# flippie.net
KiCad netlist of a schematic drawn in EAGLE
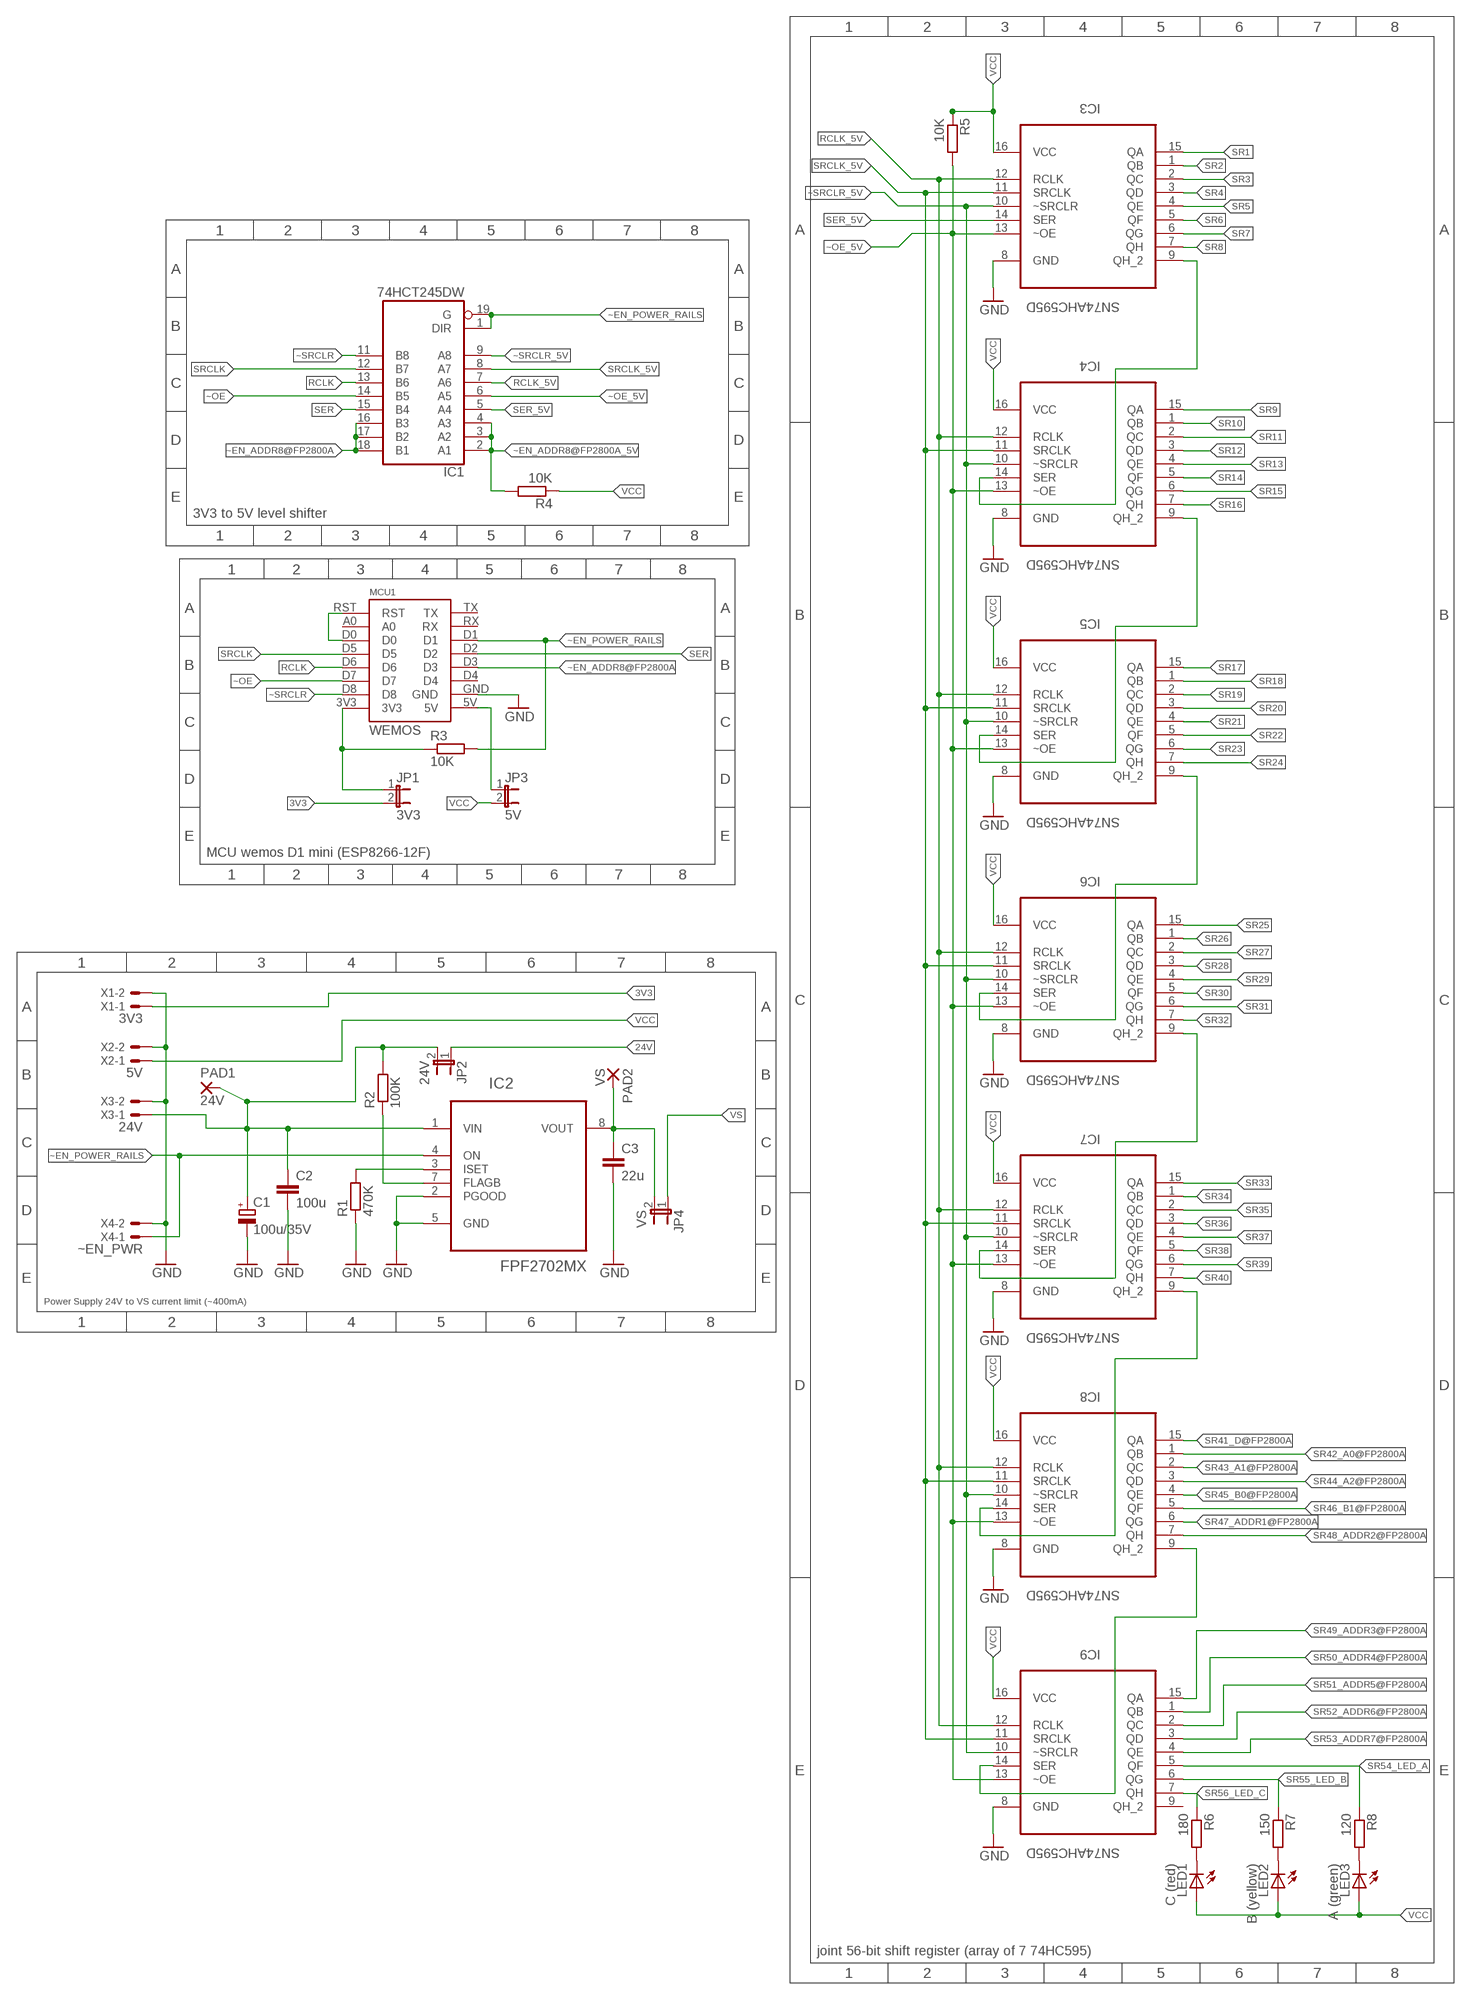
[diagram p0: schematic, sheet 1, part 1 of 2]
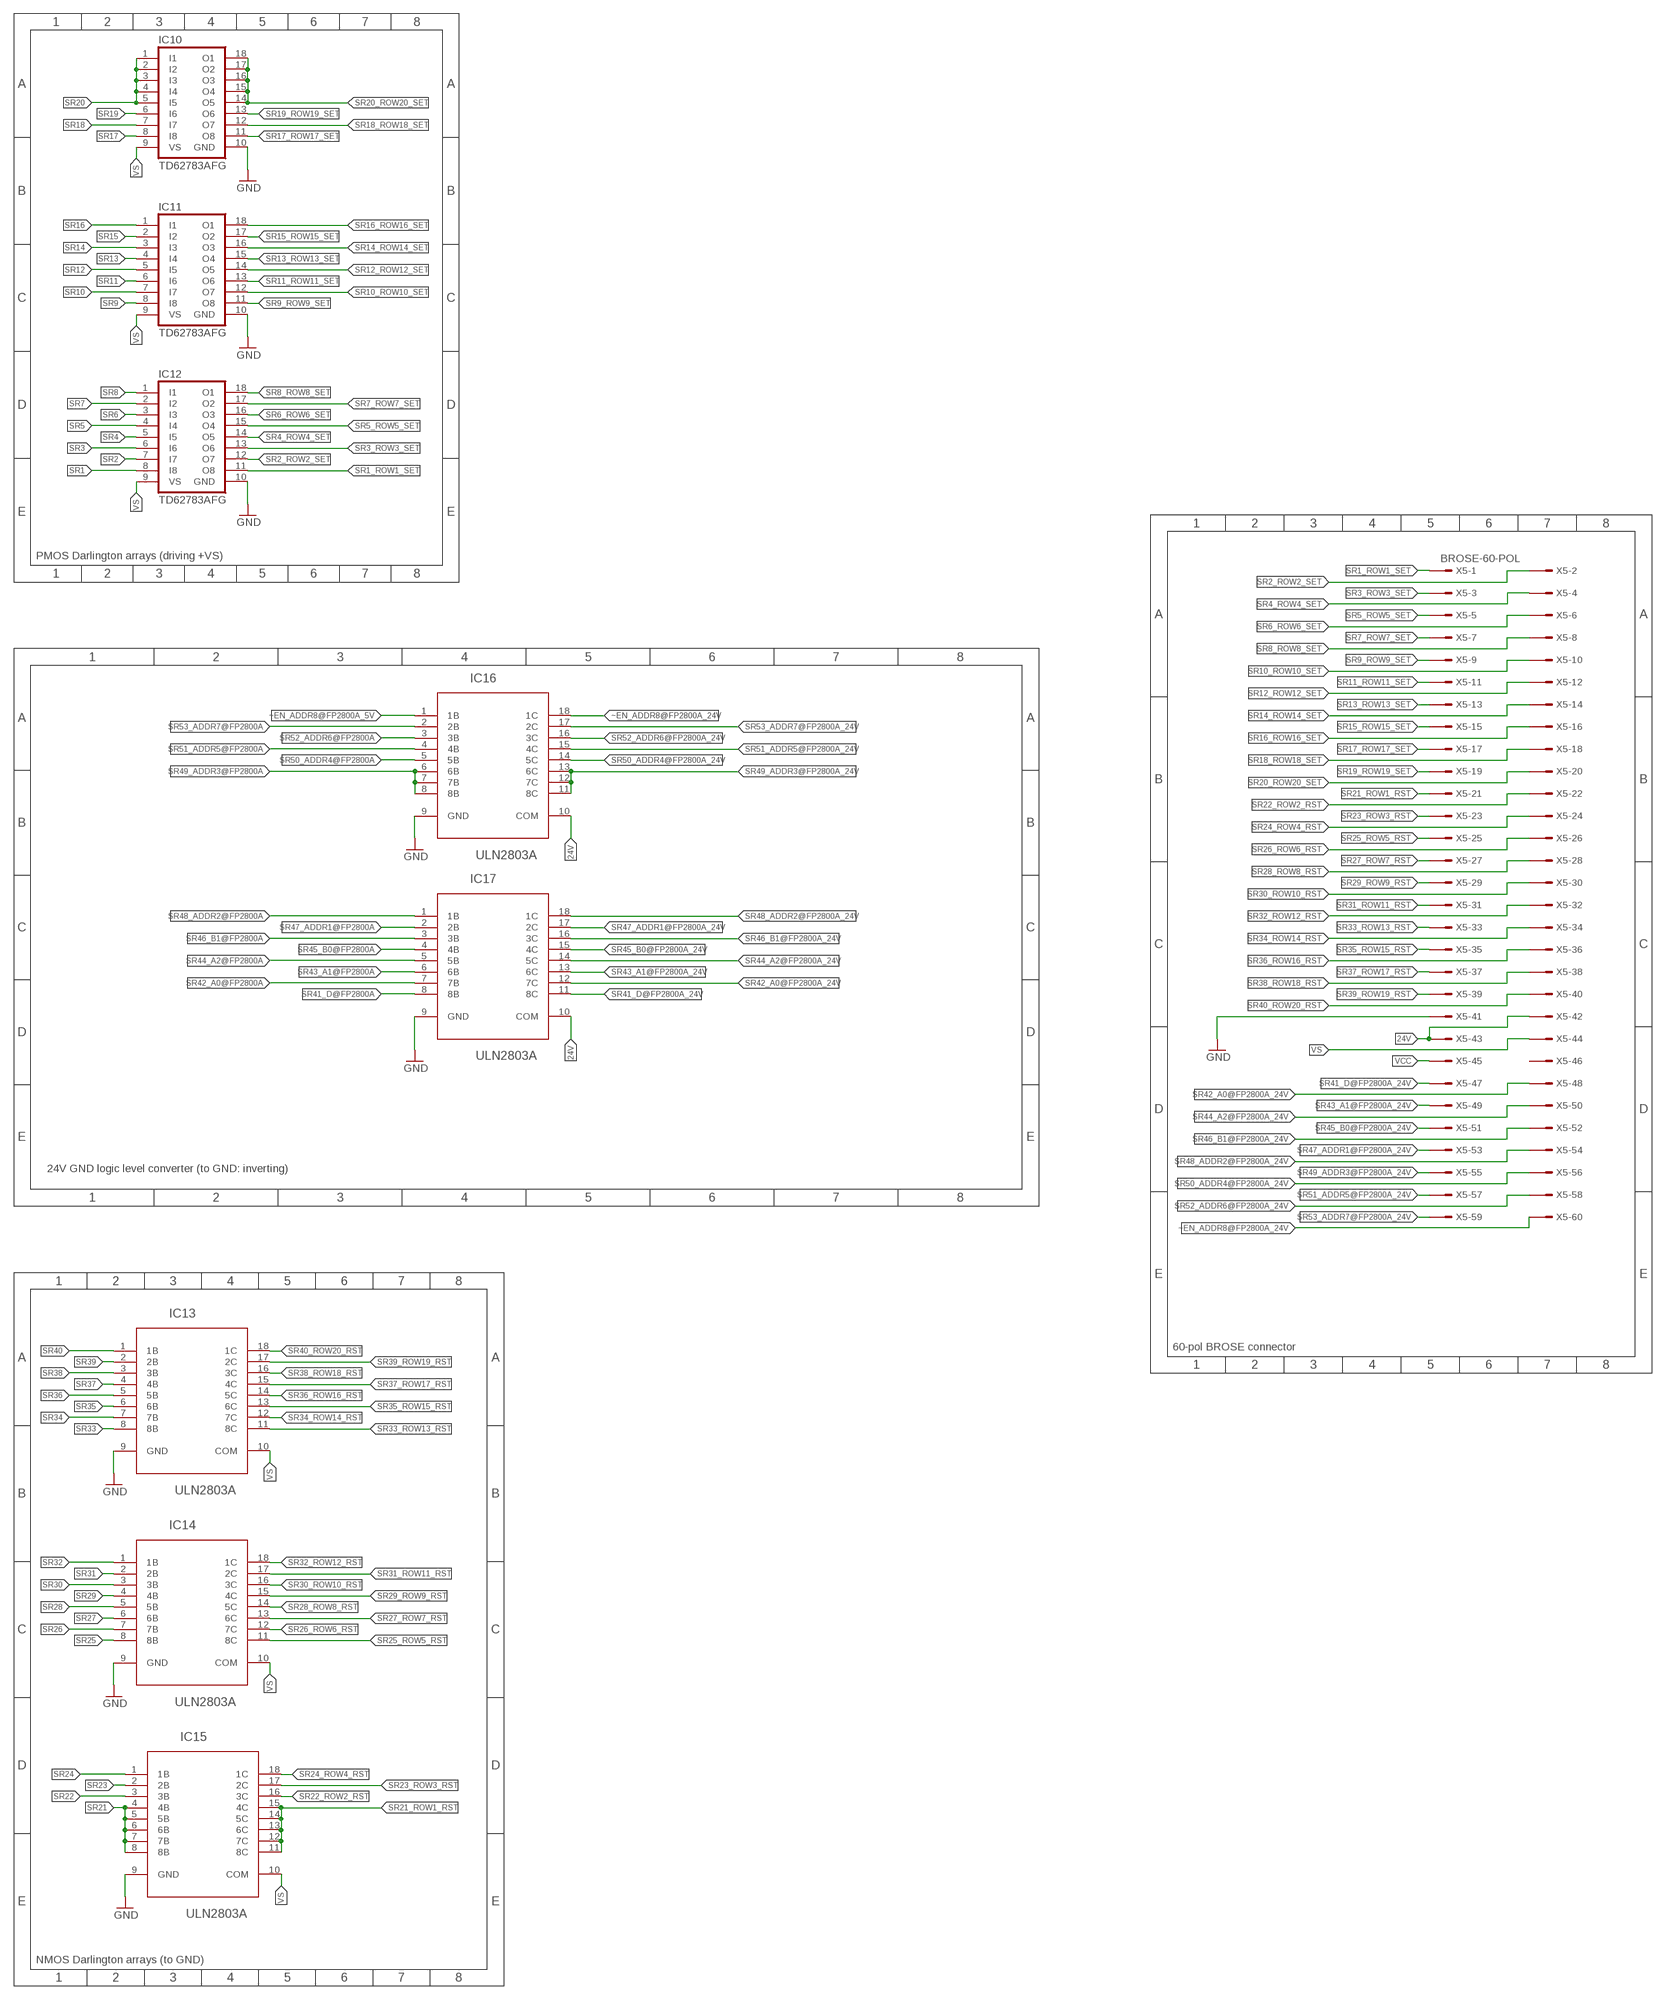
[diagram p1: schematic, sheet 1, part 2 of 2]

(export (version "E")
  (design (tool "Eeschema 10.0.6"))
  (components
    (comp (ref "C1")
      (value "100u/35V")
      (footprint "eagle-import:PANASONIC_E")
      (libsource (lib "eagle-import") (part "CPOL-EUE"))
    )
    (comp (ref "C2")
      (value "100u")
      (footprint "eagle-import:C1206")
      (libsource (lib "eagle-import") (part "C-EUC1206"))
    )
    (comp (ref "C3")
      (value "22u")
      (footprint "eagle-import:C1206")
      (libsource (lib "eagle-import") (part "C-EUC1206"))
    )
    (comp (ref "IC1")
      (value "74HCT245DW")
      (footprint "eagle-import:SO20W")
      (libsource (lib "eagle-import") (part "74245DWHCT"))
    )
    (comp (ref "IC2")
      (value "FPF2702MX")
      (footprint "eagle-import:SOIC127P600X175-8N")
      (libsource (lib "eagle-import") (part "FPF2700"))
    )
    (comp (ref "IC3")
      (value "SN74AHC595D")
      (footprint "eagle-import:SOIC127P600X175-16N")
      (libsource (lib "eagle-import") (part "SN74AHC595D"))
    )
    (comp (ref "IC4")
      (value "SN74AHC595D")
      (footprint "eagle-import:SOIC127P600X175-16N")
      (libsource (lib "eagle-import") (part "SN74AHC595D"))
    )
    (comp (ref "IC5")
      (value "SN74AHC595D")
      (footprint "eagle-import:SOIC127P600X175-16N")
      (libsource (lib "eagle-import") (part "SN74AHC595D"))
    )
    (comp (ref "IC6")
      (value "SN74AHC595D")
      (footprint "eagle-import:SOIC127P600X175-16N")
      (libsource (lib "eagle-import") (part "SN74AHC595D"))
    )
    (comp (ref "IC7")
      (value "SN74AHC595D")
      (footprint "eagle-import:SOIC127P600X175-16N")
      (libsource (lib "eagle-import") (part "SN74AHC595D"))
    )
    (comp (ref "IC8")
      (value "SN74AHC595D")
      (footprint "eagle-import:SOIC127P600X175-16N")
      (libsource (lib "eagle-import") (part "SN74AHC595D"))
    )
    (comp (ref "IC9")
      (value "SN74AHC595D")
      (footprint "eagle-import:SOIC127P600X175-16N")
      (libsource (lib "eagle-import") (part "SN74AHC595D"))
    )
    (comp (ref "IC10")
      (value "TD62783AFG")
      (footprint "eagle-import:SO18W")
      (libsource (lib "eagle-import") (part "UDN298LW1"))
    )
    (comp (ref "IC11")
      (value "TD62783AFG")
      (footprint "eagle-import:SO18W")
      (libsource (lib "eagle-import") (part "UDN298LW1"))
    )
    (comp (ref "IC12")
      (value "TD62783AFG")
      (footprint "eagle-import:SO18W")
      (libsource (lib "eagle-import") (part "UDN298LW1"))
    )
    (comp (ref "IC13")
      (value "ULN2803A")
      (footprint "eagle-import:SOIC127P1030X265-18N")
      (fields (field (name "MPN") "ULN2803ADW"))
      (libsource (lib "eagle-import") (part "ULN2803ADW"))
    )
    (comp (ref "IC14")
      (value "ULN2803A")
      (footprint "eagle-import:SOIC127P1030X265-18N")
      (fields (field (name "MPN") "ULN2803ADW"))
      (libsource (lib "eagle-import") (part "ULN2803ADW"))
    )
    (comp (ref "IC15")
      (value "ULN2803A")
      (footprint "eagle-import:SOIC127P1030X265-18N")
      (fields (field (name "MPN") "ULN2803ADW"))
      (libsource (lib "eagle-import") (part "ULN2803ADW"))
    )
    (comp (ref "IC16")
      (value "ULN2803A")
      (footprint "eagle-import:SOIC127P1030X265-18N")
      (fields (field (name "MPN") "ULN2803ADW"))
      (libsource (lib "eagle-import") (part "ULN2803ADW"))
    )
    (comp (ref "IC17")
      (value "ULN2803A")
      (footprint "eagle-import:SOIC127P1030X265-18N")
      (fields (field (name "MPN") "ULN2803ADW"))
      (libsource (lib "eagle-import") (part "ULN2803ADW"))
    )
    (comp (ref "JP1")
      (value "3V3")
      (footprint "eagle-import:JP1")
      (libsource (lib "eagle-import") (part "JP1E"))
    )
    (comp (ref "JP2")
      (value "24V")
      (footprint "eagle-import:JP1")
      (libsource (lib "eagle-import") (part "JP1E"))
    )
    (comp (ref "JP3")
      (value "5V")
      (footprint "eagle-import:JP1")
      (libsource (lib "eagle-import") (part "JP1E"))
    )
    (comp (ref "JP4")
      (value "VS")
      (footprint "eagle-import:JP1")
      (libsource (lib "eagle-import") (part "JP1E"))
    )
    (comp (ref "LED1")
      (value "C (red)")
      (footprint "eagle-import:1206")
      (libsource (lib "eagle-import") (part "LEDSMT1206"))
    )
    (comp (ref "LED2")
      (value "B (yellow)")
      (footprint "eagle-import:1206")
      (libsource (lib "eagle-import") (part "LEDSMT1206"))
    )
    (comp (ref "LED3")
      (value "A (green)")
      (footprint "eagle-import:1206")
      (libsource (lib "eagle-import") (part "LEDSMT1206"))
    )
    (comp (ref "MCU1")
      (value "WEMOS")
      (footprint "eagle-import:WEMOS")
      (libsource (lib "eagle-import") (part "WEMOS"))
    )
    (comp (ref "PAD1")
      (value "24V")
      (footprint "eagle-import:2,15_1,0")
      (libsource (lib "eagle-import") (part "2,15/1,0"))
    )
    (comp (ref "PAD2")
      (value "VS")
      (footprint "eagle-import:2,15_1,0")
      (libsource (lib "eagle-import") (part "2,15/1,0"))
    )
    (comp (ref "R1")
      (value "470K")
      (footprint "eagle-import:R1206")
      (libsource (lib "eagle-import") (part "R-EU_R1206"))
    )
    (comp (ref "R2")
      (value "100K")
      (footprint "eagle-import:R1206")
      (libsource (lib "eagle-import") (part "R-EU_R1206"))
    )
    (comp (ref "R3")
      (value "10K")
      (footprint "eagle-import:R1206")
      (libsource (lib "eagle-import") (part "R-EU_R1206"))
    )
    (comp (ref "R4")
      (value "10K")
      (footprint "eagle-import:R1206")
      (libsource (lib "eagle-import") (part "R-EU_R1206"))
    )
    (comp (ref "R5")
      (value "10K")
      (footprint "eagle-import:R1206")
      (libsource (lib "eagle-import") (part "R-EU_R1206"))
    )
    (comp (ref "R6")
      (value "180")
      (footprint "eagle-import:R1206")
      (libsource (lib "eagle-import") (part "R-EU_R1206"))
    )
    (comp (ref "R7")
      (value "150")
      (footprint "eagle-import:R1206")
      (libsource (lib "eagle-import") (part "R-EU_R1206"))
    )
    (comp (ref "R8")
      (value "120")
      (footprint "eagle-import:R1206")
      (libsource (lib "eagle-import") (part "R-EU_R1206"))
    )
    (comp (ref "X1")
      (value "3V3")
      (footprint "eagle-import:JST-XH-02-PACKAGE-LONG-PAD")
      (libsource (lib "eagle-import") (part "JST-XH-02-PIN-LONG-PAD"))
    )
    (comp (ref "X2")
      (value "5V")
      (footprint "eagle-import:JST-XH-02-PACKAGE-LONG-PAD")
      (libsource (lib "eagle-import") (part "JST-XH-02-PIN-LONG-PAD"))
    )
    (comp (ref "X3")
      (value "24V")
      (footprint "eagle-import:JST-XH-02-PACKAGE-LONG-PAD")
      (libsource (lib "eagle-import") (part "JST-XH-02-PIN-LONG-PAD"))
    )
    (comp (ref "X4")
      (value "~EN_PWR")
      (footprint "eagle-import:JST-XH-02-PACKAGE-LONG-PAD")
      (libsource (lib "eagle-import") (part "JST-XH-02-PIN-LONG-PAD"))
    )
    (comp (ref "X5")
      (value "BROSE-60-POL")
      (footprint "eagle-import:057-060-1")
      (libsource (lib "eagle-import") (part "057-060-1"))
    )
  )
  (nets
    (net (code "1") (name "/~{EN_ADDR8@FP2800A_5V}") (class "Default")
      (node (ref "IC1") (pin "2") (pinfunction "A1_2") (pintype "bidirectional"))
      (node (ref "IC1") (pin "3") (pinfunction "A2_3") (pintype "bidirectional"))
      (node (ref "IC1") (pin "4") (pinfunction "A3_4") (pintype "bidirectional"))
      (node (ref "IC16") (pin "1") (pinfunction "1B_1") (pintype "input"))
      (node (ref "R4") (pin "2") (pinfunction "2_2") (pintype "passive"))
    )
    (net (code "2") (name "/~{EN_ADDR8@FP2800A_24V}") (class "Default")
      (node (ref "IC16") (pin "18") (pinfunction "1C_18") (pintype "output"))
      (node (ref "X5") (pin "60") (pinfunction "S_60") (pintype "passive"))
    )
    (net (code "3") (name "/~{EN_ADDR8@FP2800A}") (class "Default")
      (node (ref "IC1") (pin "16") (pinfunction "B3_16") (pintype "bidirectional"))
      (node (ref "IC1") (pin "17") (pinfunction "B2_17") (pintype "bidirectional"))
      (node (ref "IC1") (pin "18") (pinfunction "B1_18") (pintype "bidirectional"))
      (node (ref "MCU1") (pin "D3") (pinfunction "D3_D3") (pintype "bidirectional"))
    )
    (net (code "4") (name "/~{EN_POWER_RAILS}") (class "Default")
      (node (ref "IC1") (pin "1") (pinfunction "DIR_1") (pintype "input"))
      (node (ref "IC1") (pin "19") (pinfunction "G_19") (pintype "input"))
      (node (ref "IC2") (pin "4") (pinfunction "ON_4") (pintype "input"))
      (node (ref "MCU1") (pin "D1") (pinfunction "D1_D1") (pintype "bidirectional"))
      (node (ref "R3") (pin "2") (pinfunction "2_2") (pintype "passive"))
      (node (ref "X4") (pin "1") (pinfunction "S_1") (pintype "passive"))
    )
    (net (code "5") (name "/~{OE_5V}") (class "Default")
      (node (ref "IC1") (pin "6") (pinfunction "A5_6") (pintype "bidirectional"))
      (node (ref "IC3") (pin "13") (pinfunction "~{OE}_13") (pintype "input"))
      (node (ref "IC4") (pin "13") (pinfunction "~{OE}_13") (pintype "input"))
      (node (ref "IC5") (pin "13") (pinfunction "~{OE}_13") (pintype "input"))
      (node (ref "IC6") (pin "13") (pinfunction "~{OE}_13") (pintype "input"))
      (node (ref "IC7") (pin "13") (pinfunction "~{OE}_13") (pintype "input"))
      (node (ref "IC8") (pin "13") (pinfunction "~{OE}_13") (pintype "input"))
      (node (ref "IC9") (pin "13") (pinfunction "~{OE}_13") (pintype "input"))
      (node (ref "R5") (pin "2") (pinfunction "2_2") (pintype "passive"))
    )
    (net (code "6") (name "/~{OE}") (class "Default")
      (node (ref "IC1") (pin "14") (pinfunction "B5_14") (pintype "bidirectional"))
      (node (ref "MCU1") (pin "D7") (pinfunction "D7_D7") (pintype "bidirectional"))
    )
    (net (code "7") (name "/~{SRCLR_5V}") (class "Default")
      (node (ref "IC1") (pin "9") (pinfunction "A8_9") (pintype "bidirectional"))
      (node (ref "IC3") (pin "10") (pinfunction "~{SRCLR}_10") (pintype "input"))
      (node (ref "IC4") (pin "10") (pinfunction "~{SRCLR}_10") (pintype "input"))
      (node (ref "IC5") (pin "10") (pinfunction "~{SRCLR}_10") (pintype "input"))
      (node (ref "IC6") (pin "10") (pinfunction "~{SRCLR}_10") (pintype "input"))
      (node (ref "IC7") (pin "10") (pinfunction "~{SRCLR}_10") (pintype "input"))
      (node (ref "IC8") (pin "10") (pinfunction "~{SRCLR}_10") (pintype "input"))
      (node (ref "IC9") (pin "10") (pinfunction "~{SRCLR}_10") (pintype "input"))
    )
    (net (code "8") (name "/~{SRCLR}") (class "Default")
      (node (ref "IC1") (pin "11") (pinfunction "B8_11") (pintype "bidirectional"))
      (node (ref "MCU1") (pin "D8") (pinfunction "D8_D8") (pintype "bidirectional"))
    )
    (net (code "9") (name "3V3") (class "Default")
      (node (ref "JP1") (pin "2") (pinfunction "2_2") (pintype "passive"))
      (node (ref "X1") (pin "1") (pinfunction "S_1") (pintype "passive"))
    )
    (net (code "10") (name "24V") (class "Default")
      (node (ref "IC16") (pin "10") (pinfunction "COM_10") (pintype "output"))
      (node (ref "IC17") (pin "10") (pinfunction "COM_10") (pintype "output"))
      (node (ref "JP2") (pin "1") (pinfunction "1_1") (pintype "passive"))
      (node (ref "X5") (pin "42") (pinfunction "S_42") (pintype "passive"))
      (node (ref "X5") (pin "43") (pinfunction "S_43") (pintype "passive"))
    )
    (net (code "11") (name "GND") (class "Default")
      (node (ref "C1") (pin "-") (pinfunction "-_-") (pintype "passive"))
      (node (ref "C2") (pin "2") (pinfunction "2_2") (pintype "passive"))
      (node (ref "C3") (pin "2") (pinfunction "2_2") (pintype "passive"))
      (node (ref "IC10") (pin "10") (pinfunction "GND_10") (pintype "power_in"))
      (node (ref "IC11") (pin "10") (pinfunction "GND_10") (pintype "power_in"))
      (node (ref "IC12") (pin "10") (pinfunction "GND_10") (pintype "power_in"))
      (node (ref "IC13") (pin "9") (pinfunction "GND_9") (pintype "passive"))
      (node (ref "IC14") (pin "9") (pinfunction "GND_9") (pintype "passive"))
      (node (ref "IC15") (pin "9") (pinfunction "GND_9") (pintype "passive"))
      (node (ref "IC16") (pin "9") (pinfunction "GND_9") (pintype "passive"))
      (node (ref "IC17") (pin "9") (pinfunction "GND_9") (pintype "passive"))
      (node (ref "IC2") (pin "2") (pinfunction "PGOOD_2") (pintype "output"))
      (node (ref "IC2") (pin "5") (pinfunction "GND_5") (pintype "passive"))
      (node (ref "IC3") (pin "8") (pinfunction "GND_8") (pintype "passive"))
      (node (ref "IC4") (pin "8") (pinfunction "GND_8") (pintype "passive"))
      (node (ref "IC5") (pin "8") (pinfunction "GND_8") (pintype "passive"))
      (node (ref "IC6") (pin "8") (pinfunction "GND_8") (pintype "passive"))
      (node (ref "IC7") (pin "8") (pinfunction "GND_8") (pintype "passive"))
      (node (ref "IC8") (pin "8") (pinfunction "GND_8") (pintype "passive"))
      (node (ref "IC9") (pin "8") (pinfunction "GND_8") (pintype "passive"))
      (node (ref "MCU1") (pin "GND") (pinfunction "GND_GND") (pintype "bidirectional"))
      (node (ref "R1") (pin "1") (pinfunction "1_1") (pintype "passive"))
      (node (ref "X1") (pin "2") (pinfunction "S_2") (pintype "passive"))
      (node (ref "X2") (pin "2") (pinfunction "S_2") (pintype "passive"))
      (node (ref "X3") (pin "2") (pinfunction "S_2") (pintype "passive"))
      (node (ref "X4") (pin "2") (pinfunction "S_2") (pintype "passive"))
      (node (ref "X5") (pin "41") (pinfunction "S_41") (pintype "passive"))
    )
    (net (code "12") (name "Net-(IC2-FLAGB)") (class "Default")
      (node (ref "IC2") (pin "7") (pinfunction "FLAGB_7") (pintype "output"))
      (node (ref "R2") (pin "1") (pinfunction "1_1") (pintype "passive"))
    )
    (net (code "13") (name "Net-(IC2-ISET)") (class "Default")
      (node (ref "IC2") (pin "3") (pinfunction "ISET_3") (pintype "input"))
      (node (ref "R1") (pin "2") (pinfunction "2_2") (pintype "passive"))
    )
    (net (code "14") (name "Net-(IC2-VIN)") (class "Default")
      (node (ref "C1") (pin "+") (pinfunction "+_+") (pintype "passive"))
      (node (ref "C2") (pin "1") (pinfunction "1_1") (pintype "passive"))
      (node (ref "IC2") (pin "1") (pinfunction "VIN_1") (pintype "power_in"))
      (node (ref "JP2") (pin "2") (pinfunction "2_2") (pintype "passive"))
      (node (ref "PAD1") (pin "1") (pinfunction "P_1") (pintype "passive"))
      (node (ref "R2") (pin "2") (pinfunction "2_2") (pintype "passive"))
      (node (ref "X3") (pin "1") (pinfunction "S_1") (pintype "passive"))
    )
    (net (code "15") (name "Net-(IC2-VOUT)") (class "Default")
      (node (ref "C3") (pin "1") (pinfunction "1_1") (pintype "passive"))
      (node (ref "IC2") (pin "8") (pinfunction "VOUT_8") (pintype "power_in"))
      (node (ref "JP4") (pin "2") (pinfunction "2_2") (pintype "passive"))
      (node (ref "PAD2") (pin "1") (pinfunction "P_1") (pintype "passive"))
    )
    (net (code "16") (name "Net-(IC3-QH_2)") (class "Default")
      (node (ref "IC3") (pin "9") (pinfunction "QH_2_9") (pintype "output"))
      (node (ref "IC4") (pin "14") (pinfunction "SER_14") (pintype "input"))
    )
    (net (code "17") (name "Net-(IC4-QH_2)") (class "Default")
      (node (ref "IC4") (pin "9") (pinfunction "QH_2_9") (pintype "output"))
      (node (ref "IC5") (pin "14") (pinfunction "SER_14") (pintype "input"))
    )
    (net (code "18") (name "Net-(IC5-QH_2)") (class "Default")
      (node (ref "IC5") (pin "9") (pinfunction "QH_2_9") (pintype "output"))
      (node (ref "IC6") (pin "14") (pinfunction "SER_14") (pintype "input"))
    )
    (net (code "19") (name "Net-(IC6-QH_2)") (class "Default")
      (node (ref "IC6") (pin "9") (pinfunction "QH_2_9") (pintype "output"))
      (node (ref "IC7") (pin "14") (pinfunction "SER_14") (pintype "input"))
    )
    (net (code "20") (name "Net-(IC7-QH_2)") (class "Default")
      (node (ref "IC7") (pin "9") (pinfunction "QH_2_9") (pintype "output"))
      (node (ref "IC8") (pin "14") (pinfunction "SER_14") (pintype "input"))
    )
    (net (code "21") (name "Net-(IC8-QH_2)") (class "Default")
      (node (ref "IC8") (pin "9") (pinfunction "QH_2_9") (pintype "output"))
      (node (ref "IC9") (pin "14") (pinfunction "SER_14") (pintype "input"))
    )
    (net (code "22") (name "Net-(JP1-Pad1)") (class "Default")
      (node (ref "JP1") (pin "1") (pinfunction "1_1") (pintype "passive"))
      (node (ref "MCU1") (pin "3V3") (pinfunction "3V3_3V3") (pintype "bidirectional"))
      (node (ref "R3") (pin "1") (pinfunction "1_1") (pintype "passive"))
    )
    (net (code "23") (name "Net-(JP3-Pad1)") (class "Default")
      (node (ref "JP3") (pin "1") (pinfunction "1_1") (pintype "passive"))
      (node (ref "MCU1") (pin "5V") (pinfunction "5V_5V") (pintype "bidirectional"))
    )
    (net (code "24") (name "Net-(LED1-PadC)") (class "Default")
      (node (ref "LED1") (pin "C") (pinfunction "C_C") (pintype "passive"))
      (node (ref "R6") (pin "2") (pinfunction "2_2") (pintype "passive"))
    )
    (net (code "25") (name "Net-(LED2-PadC)") (class "Default")
      (node (ref "LED2") (pin "C") (pinfunction "C_C") (pintype "passive"))
      (node (ref "R7") (pin "2") (pinfunction "2_2") (pintype "passive"))
    )
    (net (code "26") (name "Net-(LED3-PadC)") (class "Default")
      (node (ref "LED3") (pin "C") (pinfunction "C_C") (pintype "passive"))
      (node (ref "R8") (pin "2") (pinfunction "2_2") (pintype "passive"))
    )
    (net (code "27") (name "Net-(MCU1-PadD0)") (class "Default")
      (node (ref "MCU1") (pin "D0") (pinfunction "D0_D0") (pintype "bidirectional"))
      (node (ref "MCU1") (pin "RST") (pinfunction "RST_RST") (pintype "bidirectional"))
    )
    (net (code "28") (name "RCLK") (class "Default")
      (node (ref "IC1") (pin "13") (pinfunction "B6_13") (pintype "bidirectional"))
      (node (ref "MCU1") (pin "D6") (pinfunction "D6_D6") (pintype "bidirectional"))
    )
    (net (code "29") (name "RCLK_5V") (class "Default")
      (node (ref "IC1") (pin "7") (pinfunction "A6_7") (pintype "bidirectional"))
      (node (ref "IC3") (pin "12") (pinfunction "RCLK_12") (pintype "input"))
      (node (ref "IC4") (pin "12") (pinfunction "RCLK_12") (pintype "input"))
      (node (ref "IC5") (pin "12") (pinfunction "RCLK_12") (pintype "input"))
      (node (ref "IC6") (pin "12") (pinfunction "RCLK_12") (pintype "input"))
      (node (ref "IC7") (pin "12") (pinfunction "RCLK_12") (pintype "input"))
      (node (ref "IC8") (pin "12") (pinfunction "RCLK_12") (pintype "input"))
      (node (ref "IC9") (pin "12") (pinfunction "RCLK_12") (pintype "input"))
    )
    (net (code "30") (name "SER") (class "Default")
      (node (ref "IC1") (pin "15") (pinfunction "B4_15") (pintype "bidirectional"))
      (node (ref "MCU1") (pin "D2") (pinfunction "D2_D2") (pintype "bidirectional"))
    )
    (net (code "31") (name "SER_5V") (class "Default")
      (node (ref "IC1") (pin "5") (pinfunction "A4_5") (pintype "bidirectional"))
      (node (ref "IC3") (pin "14") (pinfunction "SER_14") (pintype "input"))
    )
    (net (code "32") (name "SR1") (class "Default")
      (node (ref "IC12") (pin "8") (pinfunction "I8_8") (pintype "input"))
      (node (ref "IC3") (pin "15") (pinfunction "QA_15") (pintype "output"))
    )
    (net (code "33") (name "SR1_ROW1_SET") (class "Default")
      (node (ref "IC12") (pin "11") (pinfunction "O8_11") (pintype "open_collector"))
      (node (ref "X5") (pin "1") (pinfunction "S_1") (pintype "passive"))
    )
    (net (code "34") (name "SR2") (class "Default")
      (node (ref "IC12") (pin "7") (pinfunction "I7_7") (pintype "input"))
      (node (ref "IC3") (pin "1") (pinfunction "QB_1") (pintype "output"))
    )
    (net (code "35") (name "SR2_ROW2_SET") (class "Default")
      (node (ref "IC12") (pin "12") (pinfunction "O7_12") (pintype "open_collector"))
      (node (ref "X5") (pin "2") (pinfunction "S_2") (pintype "passive"))
    )
    (net (code "36") (name "SR3") (class "Default")
      (node (ref "IC12") (pin "6") (pinfunction "I6_6") (pintype "input"))
      (node (ref "IC3") (pin "2") (pinfunction "QC_2") (pintype "output"))
    )
    (net (code "37") (name "SR3_ROW3_SET") (class "Default")
      (node (ref "IC12") (pin "13") (pinfunction "O6_13") (pintype "open_collector"))
      (node (ref "X5") (pin "3") (pinfunction "S_3") (pintype "passive"))
    )
    (net (code "38") (name "SR4") (class "Default")
      (node (ref "IC12") (pin "5") (pinfunction "I5_5") (pintype "input"))
      (node (ref "IC3") (pin "3") (pinfunction "QD_3") (pintype "output"))
    )
    (net (code "39") (name "SR4_ROW4_SET") (class "Default")
      (node (ref "IC12") (pin "14") (pinfunction "O5_14") (pintype "open_collector"))
      (node (ref "X5") (pin "4") (pinfunction "S_4") (pintype "passive"))
    )
    (net (code "40") (name "SR5") (class "Default")
      (node (ref "IC12") (pin "4") (pinfunction "I4_4") (pintype "input"))
      (node (ref "IC3") (pin "4") (pinfunction "QE_4") (pintype "output"))
    )
    (net (code "41") (name "SR5_ROW5_SET") (class "Default")
      (node (ref "IC12") (pin "15") (pinfunction "O4_15") (pintype "open_collector"))
      (node (ref "X5") (pin "5") (pinfunction "S_5") (pintype "passive"))
    )
    (net (code "42") (name "SR6") (class "Default")
      (node (ref "IC12") (pin "3") (pinfunction "I3_3") (pintype "input"))
      (node (ref "IC3") (pin "5") (pinfunction "QF_5") (pintype "output"))
    )
    (net (code "43") (name "SR6_ROW6_SET") (class "Default")
      (node (ref "IC12") (pin "16") (pinfunction "O3_16") (pintype "open_collector"))
      (node (ref "X5") (pin "6") (pinfunction "S_6") (pintype "passive"))
    )
    (net (code "44") (name "SR7") (class "Default")
      (node (ref "IC12") (pin "2") (pinfunction "I2_2") (pintype "input"))
      (node (ref "IC3") (pin "6") (pinfunction "QG_6") (pintype "output"))
    )
    (net (code "45") (name "SR7_ROW7_SET") (class "Default")
      (node (ref "IC12") (pin "17") (pinfunction "O2_17") (pintype "open_collector"))
      (node (ref "X5") (pin "7") (pinfunction "S_7") (pintype "passive"))
    )
    (net (code "46") (name "SR8") (class "Default")
      (node (ref "IC12") (pin "1") (pinfunction "I1_1") (pintype "input"))
      (node (ref "IC3") (pin "7") (pinfunction "QH_7") (pintype "output"))
    )
    (net (code "47") (name "SR8_ROW8_SET") (class "Default")
      (node (ref "IC12") (pin "18") (pinfunction "O1_18") (pintype "open_collector"))
      (node (ref "X5") (pin "8") (pinfunction "S_8") (pintype "passive"))
    )
    (net (code "48") (name "SR9") (class "Default")
      (node (ref "IC11") (pin "8") (pinfunction "I8_8") (pintype "input"))
      (node (ref "IC4") (pin "15") (pinfunction "QA_15") (pintype "output"))
    )
    (net (code "49") (name "SR9_ROW9_SET") (class "Default")
      (node (ref "IC11") (pin "11") (pinfunction "O8_11") (pintype "open_collector"))
      (node (ref "X5") (pin "9") (pinfunction "S_9") (pintype "passive"))
    )
    (net (code "50") (name "SR10") (class "Default")
      (node (ref "IC11") (pin "7") (pinfunction "I7_7") (pintype "input"))
      (node (ref "IC4") (pin "1") (pinfunction "QB_1") (pintype "output"))
    )
    (net (code "51") (name "SR10_ROW10_SET") (class "Default")
      (node (ref "IC11") (pin "12") (pinfunction "O7_12") (pintype "open_collector"))
      (node (ref "X5") (pin "10") (pinfunction "S_10") (pintype "passive"))
    )
    (net (code "52") (name "SR11") (class "Default")
      (node (ref "IC11") (pin "6") (pinfunction "I6_6") (pintype "input"))
      (node (ref "IC4") (pin "2") (pinfunction "QC_2") (pintype "output"))
    )
    (net (code "53") (name "SR11_ROW11_SET") (class "Default")
      (node (ref "IC11") (pin "13") (pinfunction "O6_13") (pintype "open_collector"))
      (node (ref "X5") (pin "11") (pinfunction "S_11") (pintype "passive"))
    )
    (net (code "54") (name "SR12") (class "Default")
      (node (ref "IC11") (pin "5") (pinfunction "I5_5") (pintype "input"))
      (node (ref "IC4") (pin "3") (pinfunction "QD_3") (pintype "output"))
    )
    (net (code "55") (name "SR12_ROW12_SET") (class "Default")
      (node (ref "IC11") (pin "14") (pinfunction "O5_14") (pintype "open_collector"))
      (node (ref "X5") (pin "12") (pinfunction "S_12") (pintype "passive"))
    )
    (net (code "56") (name "SR13") (class "Default")
      (node (ref "IC11") (pin "4") (pinfunction "I4_4") (pintype "input"))
      (node (ref "IC4") (pin "4") (pinfunction "QE_4") (pintype "output"))
    )
    (net (code "57") (name "SR13_ROW13_SET") (class "Default")
      (node (ref "IC11") (pin "15") (pinfunction "O4_15") (pintype "open_collector"))
      (node (ref "X5") (pin "13") (pinfunction "S_13") (pintype "passive"))
    )
    (net (code "58") (name "SR14") (class "Default")
      (node (ref "IC11") (pin "3") (pinfunction "I3_3") (pintype "input"))
      (node (ref "IC4") (pin "5") (pinfunction "QF_5") (pintype "output"))
    )
    (net (code "59") (name "SR14_ROW14_SET") (class "Default")
      (node (ref "IC11") (pin "16") (pinfunction "O3_16") (pintype "open_collector"))
      (node (ref "X5") (pin "14") (pinfunction "S_14") (pintype "passive"))
    )
    (net (code "60") (name "SR15") (class "Default")
      (node (ref "IC11") (pin "2") (pinfunction "I2_2") (pintype "input"))
      (node (ref "IC4") (pin "6") (pinfunction "QG_6") (pintype "output"))
    )
    (net (code "61") (name "SR15_ROW15_SET") (class "Default")
      (node (ref "IC11") (pin "17") (pinfunction "O2_17") (pintype "open_collector"))
      (node (ref "X5") (pin "15") (pinfunction "S_15") (pintype "passive"))
    )
    (net (code "62") (name "SR16") (class "Default")
      (node (ref "IC11") (pin "1") (pinfunction "I1_1") (pintype "input"))
      (node (ref "IC4") (pin "7") (pinfunction "QH_7") (pintype "output"))
    )
    (net (code "63") (name "SR16_ROW16_SET") (class "Default")
      (node (ref "IC11") (pin "18") (pinfunction "O1_18") (pintype "open_collector"))
      (node (ref "X5") (pin "16") (pinfunction "S_16") (pintype "passive"))
    )
    (net (code "64") (name "SR17") (class "Default")
      (node (ref "IC10") (pin "8") (pinfunction "I8_8") (pintype "input"))
      (node (ref "IC5") (pin "15") (pinfunction "QA_15") (pintype "output"))
    )
    (net (code "65") (name "SR17_ROW17_SET") (class "Default")
      (node (ref "IC10") (pin "11") (pinfunction "O8_11") (pintype "open_collector"))
      (node (ref "X5") (pin "17") (pinfunction "S_17") (pintype "passive"))
    )
    (net (code "66") (name "SR18") (class "Default")
      (node (ref "IC10") (pin "7") (pinfunction "I7_7") (pintype "input"))
      (node (ref "IC5") (pin "1") (pinfunction "QB_1") (pintype "output"))
    )
    (net (code "67") (name "SR18_ROW18_SET") (class "Default")
      (node (ref "IC10") (pin "12") (pinfunction "O7_12") (pintype "open_collector"))
      (node (ref "X5") (pin "18") (pinfunction "S_18") (pintype "passive"))
    )
    (net (code "68") (name "SR19") (class "Default")
      (node (ref "IC10") (pin "6") (pinfunction "I6_6") (pintype "input"))
      (node (ref "IC5") (pin "2") (pinfunction "QC_2") (pintype "output"))
    )
    (net (code "69") (name "SR19_ROW19_SET") (class "Default")
      (node (ref "IC10") (pin "13") (pinfunction "O6_13") (pintype "open_collector"))
      (node (ref "X5") (pin "19") (pinfunction "S_19") (pintype "passive"))
    )
    (net (code "70") (name "SR20") (class "Default")
      (node (ref "IC10") (pin "1") (pinfunction "I1_1") (pintype "input"))
      (node (ref "IC10") (pin "2") (pinfunction "I2_2") (pintype "input"))
      (node (ref "IC10") (pin "3") (pinfunction "I3_3") (pintype "input"))
      (node (ref "IC10") (pin "4") (pinfunction "I4_4") (pintype "input"))
      (node (ref "IC10") (pin "5") (pinfunction "I5_5") (pintype "input"))
      (node (ref "IC5") (pin "3") (pinfunction "QD_3") (pintype "output"))
    )
    (net (code "71") (name "SR20_ROW20_SET") (class "Default")
      (node (ref "IC10") (pin "14") (pinfunction "O5_14") (pintype "open_collector"))
      (node (ref "IC10") (pin "15") (pinfunction "O4_15") (pintype "open_collector"))
      (node (ref "IC10") (pin "16") (pinfunction "O3_16") (pintype "open_collector"))
      (node (ref "IC10") (pin "17") (pinfunction "O2_17") (pintype "open_collector"))
      (node (ref "IC10") (pin "18") (pinfunction "O1_18") (pintype "open_collector"))
      (node (ref "X5") (pin "20") (pinfunction "S_20") (pintype "passive"))
    )
    (net (code "72") (name "SR21") (class "Default")
      (node (ref "IC15") (pin "4") (pinfunction "4B_4") (pintype "input"))
      (node (ref "IC15") (pin "5") (pinfunction "5B_5") (pintype "input"))
      (node (ref "IC15") (pin "6") (pinfunction "6B_6") (pintype "input"))
      (node (ref "IC15") (pin "7") (pinfunction "7B_7") (pintype "input"))
      (node (ref "IC15") (pin "8") (pinfunction "8B_8") (pintype "input"))
      (node (ref "IC5") (pin "4") (pinfunction "QE_4") (pintype "output"))
    )
    (net (code "73") (name "SR21_ROW1_RST") (class "Default")
      (node (ref "IC15") (pin "11") (pinfunction "8C_11") (pintype "output"))
      (node (ref "IC15") (pin "12") (pinfunction "7C_12") (pintype "output"))
      (node (ref "IC15") (pin "13") (pinfunction "6C_13") (pintype "output"))
      (node (ref "IC15") (pin "14") (pinfunction "5C_14") (pintype "output"))
      (node (ref "IC15") (pin "15") (pinfunction "4C_15") (pintype "output"))
      (node (ref "X5") (pin "21") (pinfunction "S_21") (pintype "passive"))
    )
    (net (code "74") (name "SR22") (class "Default")
      (node (ref "IC15") (pin "3") (pinfunction "3B_3") (pintype "input"))
      (node (ref "IC5") (pin "5") (pinfunction "QF_5") (pintype "output"))
    )
    (net (code "75") (name "SR22_ROW2_RST") (class "Default")
      (node (ref "IC15") (pin "16") (pinfunction "3C_16") (pintype "output"))
      (node (ref "X5") (pin "22") (pinfunction "S_22") (pintype "passive"))
    )
    (net (code "76") (name "SR23") (class "Default")
      (node (ref "IC15") (pin "2") (pinfunction "2B_2") (pintype "input"))
      (node (ref "IC5") (pin "6") (pinfunction "QG_6") (pintype "output"))
    )
    (net (code "77") (name "SR23_ROW3_RST") (class "Default")
      (node (ref "IC15") (pin "17") (pinfunction "2C_17") (pintype "output"))
      (node (ref "X5") (pin "23") (pinfunction "S_23") (pintype "passive"))
    )
    (net (code "78") (name "SR24") (class "Default")
      (node (ref "IC15") (pin "1") (pinfunction "1B_1") (pintype "input"))
      (node (ref "IC5") (pin "7") (pinfunction "QH_7") (pintype "output"))
    )
    (net (code "79") (name "SR24_ROW4_RST") (class "Default")
      (node (ref "IC15") (pin "18") (pinfunction "1C_18") (pintype "output"))
      (node (ref "X5") (pin "24") (pinfunction "S_24") (pintype "passive"))
    )
    (net (code "80") (name "SR25") (class "Default")
      (node (ref "IC14") (pin "8") (pinfunction "8B_8") (pintype "input"))
      (node (ref "IC6") (pin "15") (pinfunction "QA_15") (pintype "output"))
    )
    (net (code "81") (name "SR25_ROW5_RST") (class "Default")
      (node (ref "IC14") (pin "11") (pinfunction "8C_11") (pintype "output"))
      (node (ref "X5") (pin "25") (pinfunction "S_25") (pintype "passive"))
    )
    (net (code "82") (name "SR26") (class "Default")
      (node (ref "IC14") (pin "7") (pinfunction "7B_7") (pintype "input"))
      (node (ref "IC6") (pin "1") (pinfunction "QB_1") (pintype "output"))
    )
    (net (code "83") (name "SR26_ROW6_RST") (class "Default")
      (node (ref "IC14") (pin "12") (pinfunction "7C_12") (pintype "output"))
      (node (ref "X5") (pin "26") (pinfunction "S_26") (pintype "passive"))
    )
    (net (code "84") (name "SR27") (class "Default")
      (node (ref "IC14") (pin "6") (pinfunction "6B_6") (pintype "input"))
      (node (ref "IC6") (pin "2") (pinfunction "QC_2") (pintype "output"))
    )
    (net (code "85") (name "SR27_ROW7_RST") (class "Default")
      (node (ref "IC14") (pin "13") (pinfunction "6C_13") (pintype "output"))
      (node (ref "X5") (pin "27") (pinfunction "S_27") (pintype "passive"))
    )
    (net (code "86") (name "SR28") (class "Default")
      (node (ref "IC14") (pin "5") (pinfunction "5B_5") (pintype "input"))
      (node (ref "IC6") (pin "3") (pinfunction "QD_3") (pintype "output"))
    )
    (net (code "87") (name "SR28_ROW8_RST") (class "Default")
      (node (ref "IC14") (pin "14") (pinfunction "5C_14") (pintype "output"))
      (node (ref "X5") (pin "28") (pinfunction "S_28") (pintype "passive"))
    )
    (net (code "88") (name "SR29") (class "Default")
      (node (ref "IC14") (pin "4") (pinfunction "4B_4") (pintype "input"))
      (node (ref "IC6") (pin "4") (pinfunction "QE_4") (pintype "output"))
    )
    (net (code "89") (name "SR29_ROW9_RST") (class "Default")
      (node (ref "IC14") (pin "15") (pinfunction "4C_15") (pintype "output"))
      (node (ref "X5") (pin "29") (pinfunction "S_29") (pintype "passive"))
    )
    (net (code "90") (name "SR30") (class "Default")
      (node (ref "IC14") (pin "3") (pinfunction "3B_3") (pintype "input"))
      (node (ref "IC6") (pin "5") (pinfunction "QF_5") (pintype "output"))
    )
    (net (code "91") (name "SR30_ROW10_RST") (class "Default")
      (node (ref "IC14") (pin "16") (pinfunction "3C_16") (pintype "output"))
      (node (ref "X5") (pin "30") (pinfunction "S_30") (pintype "passive"))
    )
    (net (code "92") (name "SR31") (class "Default")
      (node (ref "IC14") (pin "2") (pinfunction "2B_2") (pintype "input"))
      (node (ref "IC6") (pin "6") (pinfunction "QG_6") (pintype "output"))
    )
    (net (code "93") (name "SR31_ROW11_RST") (class "Default")
      (node (ref "IC14") (pin "17") (pinfunction "2C_17") (pintype "output"))
      (node (ref "X5") (pin "31") (pinfunction "S_31") (pintype "passive"))
    )
    (net (code "94") (name "SR32") (class "Default")
      (node (ref "IC14") (pin "1") (pinfunction "1B_1") (pintype "input"))
      (node (ref "IC6") (pin "7") (pinfunction "QH_7") (pintype "output"))
    )
    (net (code "95") (name "SR32_ROW12_RST") (class "Default")
      (node (ref "IC14") (pin "18") (pinfunction "1C_18") (pintype "output"))
      (node (ref "X5") (pin "32") (pinfunction "S_32") (pintype "passive"))
    )
    (net (code "96") (name "SR33") (class "Default")
      (node (ref "IC13") (pin "8") (pinfunction "8B_8") (pintype "input"))
      (node (ref "IC7") (pin "15") (pinfunction "QA_15") (pintype "output"))
    )
    (net (code "97") (name "SR33_ROW13_RST") (class "Default")
      (node (ref "IC13") (pin "11") (pinfunction "8C_11") (pintype "output"))
      (node (ref "X5") (pin "33") (pinfunction "S_33") (pintype "passive"))
    )
    (net (code "98") (name "SR34") (class "Default")
      (node (ref "IC13") (pin "7") (pinfunction "7B_7") (pintype "input"))
      (node (ref "IC7") (pin "1") (pinfunction "QB_1") (pintype "output"))
    )
    (net (code "99") (name "SR34_ROW14_RST") (class "Default")
      (node (ref "IC13") (pin "12") (pinfunction "7C_12") (pintype "output"))
      (node (ref "X5") (pin "34") (pinfunction "S_34") (pintype "passive"))
    )
    (net (code "100") (name "SR35") (class "Default")
      (node (ref "IC13") (pin "6") (pinfunction "6B_6") (pintype "input"))
      (node (ref "IC7") (pin "2") (pinfunction "QC_2") (pintype "output"))
    )
    (net (code "101") (name "SR35_ROW15_RST") (class "Default")
      (node (ref "IC13") (pin "13") (pinfunction "6C_13") (pintype "output"))
      (node (ref "X5") (pin "35") (pinfunction "S_35") (pintype "passive"))
    )
    (net (code "102") (name "SR36") (class "Default")
      (node (ref "IC13") (pin "5") (pinfunction "5B_5") (pintype "input"))
      (node (ref "IC7") (pin "3") (pinfunction "QD_3") (pintype "output"))
    )
    (net (code "103") (name "SR36_ROW16_RST") (class "Default")
      (node (ref "IC13") (pin "14") (pinfunction "5C_14") (pintype "output"))
      (node (ref "X5") (pin "36") (pinfunction "S_36") (pintype "passive"))
    )
    (net (code "104") (name "SR37") (class "Default")
      (node (ref "IC13") (pin "4") (pinfunction "4B_4") (pintype "input"))
      (node (ref "IC7") (pin "4") (pinfunction "QE_4") (pintype "output"))
    )
    (net (code "105") (name "SR37_ROW17_RST") (class "Default")
      (node (ref "IC13") (pin "15") (pinfunction "4C_15") (pintype "output"))
      (node (ref "X5") (pin "37") (pinfunction "S_37") (pintype "passive"))
    )
    (net (code "106") (name "SR38") (class "Default")
      (node (ref "IC13") (pin "3") (pinfunction "3B_3") (pintype "input"))
      (node (ref "IC7") (pin "5") (pinfunction "QF_5") (pintype "output"))
    )
    (net (code "107") (name "SR38_ROW18_RST") (class "Default")
      (node (ref "IC13") (pin "16") (pinfunction "3C_16") (pintype "output"))
      (node (ref "X5") (pin "38") (pinfunction "S_38") (pintype "passive"))
    )
    (net (code "108") (name "SR39") (class "Default")
      (node (ref "IC13") (pin "2") (pinfunction "2B_2") (pintype "input"))
      (node (ref "IC7") (pin "6") (pinfunction "QG_6") (pintype "output"))
    )
    (net (code "109") (name "SR39_ROW19_RST") (class "Default")
      (node (ref "IC13") (pin "17") (pinfunction "2C_17") (pintype "output"))
      (node (ref "X5") (pin "39") (pinfunction "S_39") (pintype "passive"))
    )
    (net (code "110") (name "SR40") (class "Default")
      (node (ref "IC13") (pin "1") (pinfunction "1B_1") (pintype "input"))
      (node (ref "IC7") (pin "7") (pinfunction "QH_7") (pintype "output"))
    )
    (net (code "111") (name "SR40_ROW20_RST") (class "Default")
      (node (ref "IC13") (pin "18") (pinfunction "1C_18") (pintype "output"))
      (node (ref "X5") (pin "40") (pinfunction "S_40") (pintype "passive"))
    )
    (net (code "112") (name "SR41_D@FP2800A") (class "Default")
      (node (ref "IC17") (pin "8") (pinfunction "8B_8") (pintype "input"))
      (node (ref "IC8") (pin "15") (pinfunction "QA_15") (pintype "output"))
    )
    (net (code "113") (name "SR41_D@FP2800A_24V") (class "Default")
      (node (ref "IC17") (pin "11") (pinfunction "8C_11") (pintype "output"))
      (node (ref "X5") (pin "47") (pinfunction "S_47") (pintype "passive"))
    )
    (net (code "114") (name "SR42_A0@FP2800A") (class "Default")
      (node (ref "IC17") (pin "7") (pinfunction "7B_7") (pintype "input"))
      (node (ref "IC8") (pin "1") (pinfunction "QB_1") (pintype "output"))
    )
    (net (code "115") (name "SR42_A0@FP2800A_24V") (class "Default")
      (node (ref "IC17") (pin "12") (pinfunction "7C_12") (pintype "output"))
      (node (ref "X5") (pin "48") (pinfunction "S_48") (pintype "passive"))
    )
    (net (code "116") (name "SR43_A1@FP2800A") (class "Default")
      (node (ref "IC17") (pin "6") (pinfunction "6B_6") (pintype "input"))
      (node (ref "IC8") (pin "2") (pinfunction "QC_2") (pintype "output"))
    )
    (net (code "117") (name "SR43_A1@FP2800A_24V") (class "Default")
      (node (ref "IC17") (pin "13") (pinfunction "6C_13") (pintype "output"))
      (node (ref "X5") (pin "49") (pinfunction "S_49") (pintype "passive"))
    )
    (net (code "118") (name "SR44_A2@FP2800A") (class "Default")
      (node (ref "IC17") (pin "5") (pinfunction "5B_5") (pintype "input"))
      (node (ref "IC8") (pin "3") (pinfunction "QD_3") (pintype "output"))
    )
    (net (code "119") (name "SR44_A2@FP2800A_24V") (class "Default")
      (node (ref "IC17") (pin "14") (pinfunction "5C_14") (pintype "output"))
      (node (ref "X5") (pin "50") (pinfunction "S_50") (pintype "passive"))
    )
    (net (code "120") (name "SR45_B0@FP2800A") (class "Default")
      (node (ref "IC17") (pin "4") (pinfunction "4B_4") (pintype "input"))
      (node (ref "IC8") (pin "4") (pinfunction "QE_4") (pintype "output"))
    )
    (net (code "121") (name "SR45_B0@FP2800A_24V") (class "Default")
      (node (ref "IC17") (pin "15") (pinfunction "4C_15") (pintype "output"))
      (node (ref "X5") (pin "51") (pinfunction "S_51") (pintype "passive"))
    )
    (net (code "122") (name "SR46_B1@FP2800A") (class "Default")
      (node (ref "IC17") (pin "3") (pinfunction "3B_3") (pintype "input"))
      (node (ref "IC8") (pin "5") (pinfunction "QF_5") (pintype "output"))
    )
    (net (code "123") (name "SR46_B1@FP2800A_24V") (class "Default")
      (node (ref "IC17") (pin "16") (pinfunction "3C_16") (pintype "output"))
      (node (ref "X5") (pin "52") (pinfunction "S_52") (pintype "passive"))
    )
    (net (code "124") (name "SR47_ADDR1@FP2800A") (class "Default")
      (node (ref "IC17") (pin "2") (pinfunction "2B_2") (pintype "input"))
      (node (ref "IC8") (pin "6") (pinfunction "QG_6") (pintype "output"))
    )
    (net (code "125") (name "SR47_ADDR1@FP2800A_24V") (class "Default")
      (node (ref "IC17") (pin "17") (pinfunction "2C_17") (pintype "output"))
      (node (ref "X5") (pin "53") (pinfunction "S_53") (pintype "passive"))
    )
    (net (code "126") (name "SR48_ADDR2@FP2800A") (class "Default")
      (node (ref "IC17") (pin "1") (pinfunction "1B_1") (pintype "input"))
      (node (ref "IC8") (pin "7") (pinfunction "QH_7") (pintype "output"))
    )
    (net (code "127") (name "SR48_ADDR2@FP2800A_24V") (class "Default")
      (node (ref "IC17") (pin "18") (pinfunction "1C_18") (pintype "output"))
      (node (ref "X5") (pin "54") (pinfunction "S_54") (pintype "passive"))
    )
    (net (code "128") (name "SR49_ADDR3@FP2800A") (class "Default")
      (node (ref "IC16") (pin "6") (pinfunction "6B_6") (pintype "input"))
      (node (ref "IC16") (pin "7") (pinfunction "7B_7") (pintype "input"))
      (node (ref "IC16") (pin "8") (pinfunction "8B_8") (pintype "input"))
      (node (ref "IC9") (pin "15") (pinfunction "QA_15") (pintype "output"))
    )
    (net (code "129") (name "SR49_ADDR3@FP2800A_24V") (class "Default")
      (node (ref "IC16") (pin "11") (pinfunction "8C_11") (pintype "output"))
      (node (ref "IC16") (pin "12") (pinfunction "7C_12") (pintype "output"))
      (node (ref "IC16") (pin "13") (pinfunction "6C_13") (pintype "output"))
      (node (ref "X5") (pin "55") (pinfunction "S_55") (pintype "passive"))
    )
    (net (code "130") (name "SR50_ADDR4@FP2800A") (class "Default")
      (node (ref "IC16") (pin "5") (pinfunction "5B_5") (pintype "input"))
      (node (ref "IC9") (pin "1") (pinfunction "QB_1") (pintype "output"))
    )
    (net (code "131") (name "SR50_ADDR4@FP2800A_24V") (class "Default")
      (node (ref "IC16") (pin "14") (pinfunction "5C_14") (pintype "output"))
      (node (ref "X5") (pin "56") (pinfunction "S_56") (pintype "passive"))
    )
    (net (code "132") (name "SR51_ADDR5@FP2800A") (class "Default")
      (node (ref "IC16") (pin "4") (pinfunction "4B_4") (pintype "input"))
      (node (ref "IC9") (pin "2") (pinfunction "QC_2") (pintype "output"))
    )
    (net (code "133") (name "SR51_ADDR5@FP2800A_24V") (class "Default")
      (node (ref "IC16") (pin "15") (pinfunction "4C_15") (pintype "output"))
      (node (ref "X5") (pin "57") (pinfunction "S_57") (pintype "passive"))
    )
    (net (code "134") (name "SR52_ADDR6@FP2800A") (class "Default")
      (node (ref "IC16") (pin "3") (pinfunction "3B_3") (pintype "input"))
      (node (ref "IC9") (pin "3") (pinfunction "QD_3") (pintype "output"))
    )
    (net (code "135") (name "SR52_ADDR6@FP2800A_24V") (class "Default")
      (node (ref "IC16") (pin "16") (pinfunction "3C_16") (pintype "output"))
      (node (ref "X5") (pin "58") (pinfunction "S_58") (pintype "passive"))
    )
    (net (code "136") (name "SR53_ADDR7@FP2800A") (class "Default")
      (node (ref "IC16") (pin "2") (pinfunction "2B_2") (pintype "input"))
      (node (ref "IC9") (pin "4") (pinfunction "QE_4") (pintype "output"))
    )
    (net (code "137") (name "SR53_ADDR7@FP2800A_24V") (class "Default")
      (node (ref "IC16") (pin "17") (pinfunction "2C_17") (pintype "output"))
      (node (ref "X5") (pin "59") (pinfunction "S_59") (pintype "passive"))
    )
    (net (code "138") (name "SR54_LED_A") (class "Default")
      (node (ref "IC9") (pin "5") (pinfunction "QF_5") (pintype "output"))
      (node (ref "R8") (pin "1") (pinfunction "1_1") (pintype "passive"))
    )
    (net (code "139") (name "SR55_LED_B") (class "Default")
      (node (ref "IC9") (pin "6") (pinfunction "QG_6") (pintype "output"))
      (node (ref "R7") (pin "1") (pinfunction "1_1") (pintype "passive"))
    )
    (net (code "140") (name "SR56_LED_C") (class "Default")
      (node (ref "IC9") (pin "7") (pinfunction "QH_7") (pintype "output"))
      (node (ref "R6") (pin "1") (pinfunction "1_1") (pintype "passive"))
    )
    (net (code "141") (name "SRCLK") (class "Default")
      (node (ref "IC1") (pin "12") (pinfunction "B7_12") (pintype "bidirectional"))
      (node (ref "MCU1") (pin "D5") (pinfunction "D5_D5") (pintype "bidirectional"))
    )
    (net (code "142") (name "SRCLK_5V") (class "Default")
      (node (ref "IC1") (pin "8") (pinfunction "A7_8") (pintype "bidirectional"))
      (node (ref "IC3") (pin "11") (pinfunction "SRCLK_11") (pintype "input"))
      (node (ref "IC4") (pin "11") (pinfunction "SRCLK_11") (pintype "input"))
      (node (ref "IC5") (pin "11") (pinfunction "SRCLK_11") (pintype "input"))
      (node (ref "IC6") (pin "11") (pinfunction "SRCLK_11") (pintype "input"))
      (node (ref "IC7") (pin "11") (pinfunction "SRCLK_11") (pintype "input"))
      (node (ref "IC8") (pin "11") (pinfunction "SRCLK_11") (pintype "input"))
      (node (ref "IC9") (pin "11") (pinfunction "SRCLK_11") (pintype "input"))
    )
    (net (code "143") (name "VCC") (class "Default")
      (node (ref "IC3") (pin "16") (pinfunction "VCC_16") (pintype "power_in"))
      (node (ref "IC4") (pin "16") (pinfunction "VCC_16") (pintype "power_in"))
      (node (ref "IC5") (pin "16") (pinfunction "VCC_16") (pintype "power_in"))
      (node (ref "IC6") (pin "16") (pinfunction "VCC_16") (pintype "power_in"))
      (node (ref "IC7") (pin "16") (pinfunction "VCC_16") (pintype "power_in"))
      (node (ref "IC8") (pin "16") (pinfunction "VCC_16") (pintype "power_in"))
      (node (ref "IC9") (pin "16") (pinfunction "VCC_16") (pintype "power_in"))
      (node (ref "JP3") (pin "2") (pinfunction "2_2") (pintype "passive"))
      (node (ref "LED1") (pin "A") (pinfunction "A_A") (pintype "passive"))
      (node (ref "LED2") (pin "A") (pinfunction "A_A") (pintype "passive"))
      (node (ref "LED3") (pin "A") (pinfunction "A_A") (pintype "passive"))
      (node (ref "R4") (pin "1") (pinfunction "1_1") (pintype "passive"))
      (node (ref "R5") (pin "1") (pinfunction "1_1") (pintype "passive"))
      (node (ref "X2") (pin "1") (pinfunction "S_1") (pintype "passive"))
      (node (ref "X5") (pin "45") (pinfunction "S_45") (pintype "passive"))
    )
    (net (code "144") (name "VS") (class "Default")
      (node (ref "IC10") (pin "9") (pinfunction "VS_9") (pintype "passive"))
      (node (ref "IC11") (pin "9") (pinfunction "VS_9") (pintype "passive"))
      (node (ref "IC12") (pin "9") (pinfunction "VS_9") (pintype "passive"))
      (node (ref "IC13") (pin "10") (pinfunction "COM_10") (pintype "output"))
      (node (ref "IC14") (pin "10") (pinfunction "COM_10") (pintype "output"))
      (node (ref "IC15") (pin "10") (pinfunction "COM_10") (pintype "output"))
      (node (ref "JP4") (pin "1") (pinfunction "1_1") (pintype "passive"))
      (node (ref "X5") (pin "44") (pinfunction "S_44") (pintype "passive"))
    )
    (net (code "145") (name "unconnected-(IC9-QH_2-Pad9)") (class "Default")
      (node (ref "IC9") (pin "9") (pinfunction "QH_2_9") (pintype "output"))
    )
    (net (code "146") (name "unconnected-(MCU1-PadA0)") (class "Default")
      (node (ref "MCU1") (pin "A0") (pinfunction "A0_A0") (pintype "bidirectional"))
    )
    (net (code "147") (name "unconnected-(MCU1-PadD4)") (class "Default")
      (node (ref "MCU1") (pin "D4") (pinfunction "D4_D4") (pintype "bidirectional"))
    )
    (net (code "148") (name "unconnected-(MCU1-PadRX)") (class "Default")
      (node (ref "MCU1") (pin "RX") (pinfunction "RX_RX") (pintype "bidirectional"))
    )
    (net (code "149") (name "unconnected-(MCU1-PadTX)") (class "Default")
      (node (ref "MCU1") (pin "TX") (pinfunction "TX_TX") (pintype "bidirectional"))
    )
    (net (code "150") (name "unconnected-(X5AO-S-Pad46)") (class "Default")
      (node (ref "X5") (pin "46") (pinfunction "S_46") (pintype "passive"))
    )
  )
)
